# TransistorKeyBoard.net
KiCad netlist of a schematic drawn in Altium Designer
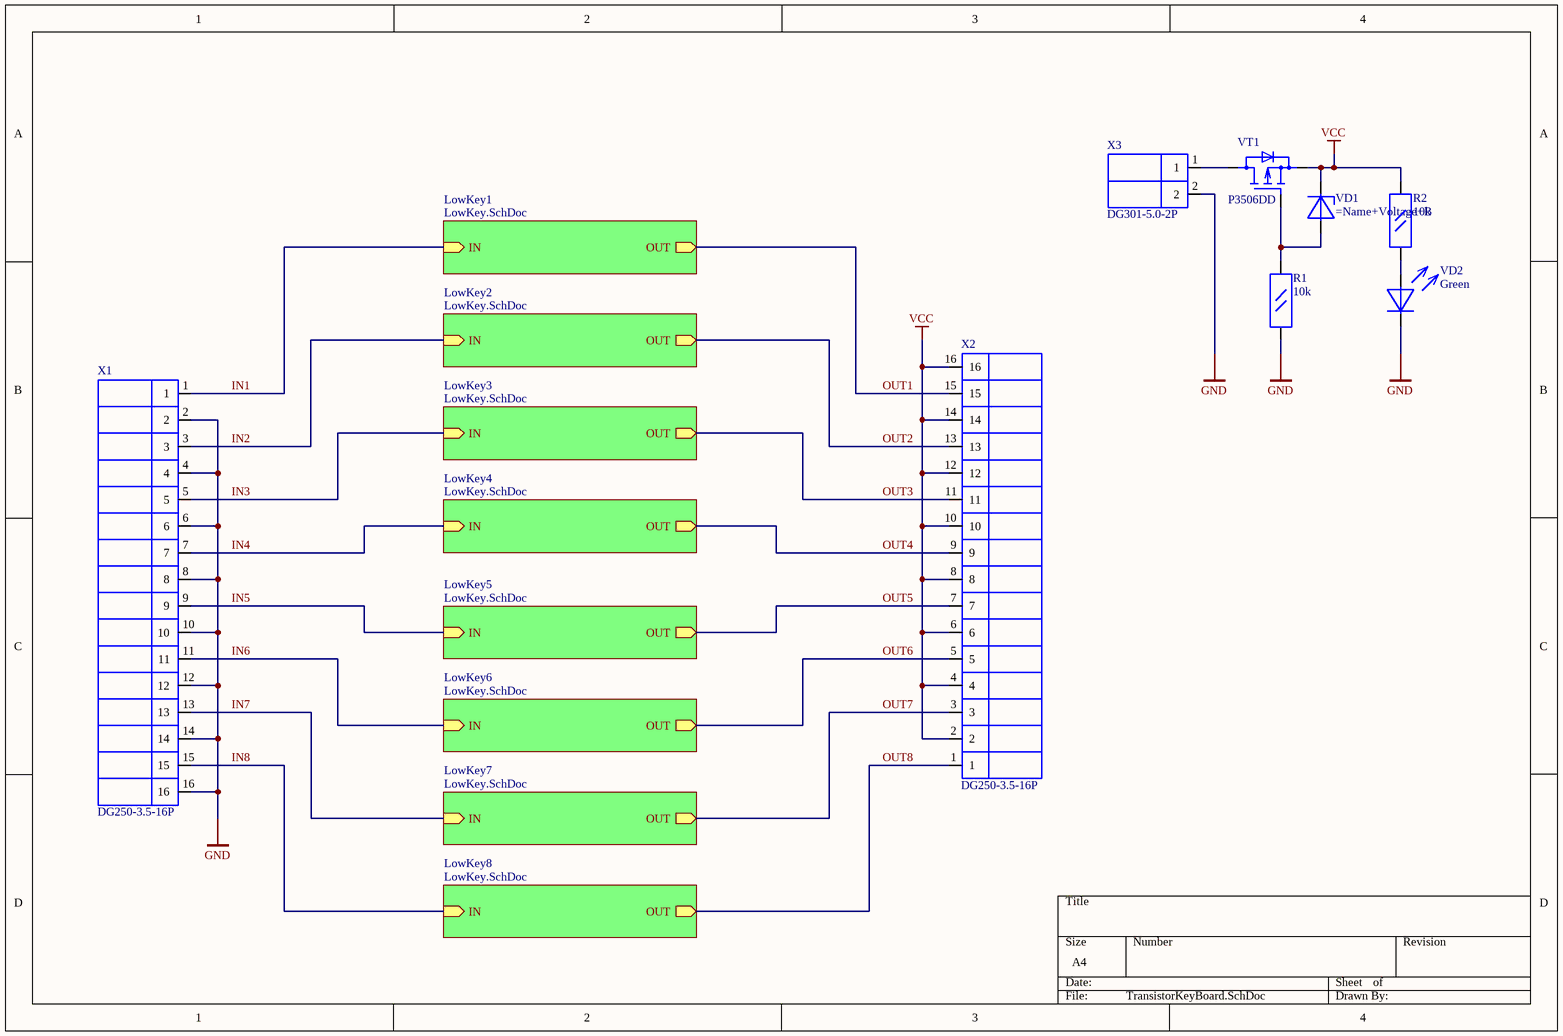
[diagram p0: TransistorKeyBoard.SchDoc]

(export (version "E")
  (design (tool "Eeschema 10.0.6"))
  (components
    (comp (ref "R1")
      (value "R0805")
      (footprint "RES0805")
      (description "Resistor")
      (fields (field (name "RESISTANCE (OHMS)") "10k"))
      (libsource (lib "zvemake_int_lib") (part "R0805"))
    )
    (comp (ref "R2")
      (value "R0805")
      (footprint "RES0805")
      (description "Resistor")
      (fields (field (name "RESISTANCE (OHMS)") "10k"))
      (libsource (lib "zvemake_int_lib") (part "R0805"))
    )
    (comp (ref "VD1")
      (value "PDZ12")
      (footprint "SOD323")
      (description "Diode")
      (fields (field (name "VOLTAGE") "12"))
      (libsource (lib "zvemake_int_lib") (part "PDZ-B"))
    )
    (comp (ref "VD2")
      (value "Led Green 3mm")
      (footprint "3mm led green")
      (description "3mm Green Led 2.54pitch")
      (fields (field (name "COLOR") "Green"))
      (libsource (lib "zvemake_int_lib") (part "Led Green 3mm"))
    )
    (comp (ref "VT1")
      (value "P3506DD")
      (footprint "DPAK")
      (description "P-channel MOSFET transistor")
      (fields (field (name "MANUFACTURER") "NIKO SEMICONDUCTOR CO"))
      (libsource (lib "zvemake_int_lib") (part "P3506DD"))
    )
    (comp (ref "X1")
      (value "DG250-3.5-16P")
      (footprint "DG250-3.5-16P")
      (description "5mm Pitch PCB Terminal Block Connector")
      (libsource (lib "zvemake_int_lib") (part "DG250-3.5-16P"))
    )
    (comp (ref "X2")
      (value "DG250-3.5-16P")
      (footprint "DG250-3.5-16P")
      (description "5mm Pitch PCB Terminal Block Connector")
      (libsource (lib "zvemake_int_lib") (part "DG250-3.5-16P"))
    )
    (comp (ref "X3")
      (value "DG301-5.0-2P")
      (footprint "DG301-5.0-2P")
      (description "5mm Pitch PCB Terminal Block Connector")
      (libsource (lib "zvemake_int_lib") (part "DG301-5.0-2P"))
    )
  )
  (nets
    (net (code "1") (name "/IN1") (class "Default")
      (node (ref "X1") (pin "1") (pinfunction "1_1") (pintype "passive"))
    )
    (net (code "2") (name "/IN2") (class "Default")
      (node (ref "X1") (pin "3") (pinfunction "3_3") (pintype "passive"))
    )
    (net (code "3") (name "/IN3") (class "Default")
      (node (ref "X1") (pin "5") (pinfunction "5_5") (pintype "passive"))
    )
    (net (code "4") (name "/IN4") (class "Default")
      (node (ref "X1") (pin "7") (pinfunction "7_7") (pintype "passive"))
    )
    (net (code "5") (name "/IN5") (class "Default")
      (node (ref "X1") (pin "9") (pinfunction "9_9") (pintype "passive"))
    )
    (net (code "6") (name "/IN6") (class "Default")
      (node (ref "X1") (pin "11") (pinfunction "11_11") (pintype "passive"))
    )
    (net (code "7") (name "/IN7") (class "Default")
      (node (ref "X1") (pin "13") (pinfunction "13_13") (pintype "passive"))
    )
    (net (code "8") (name "/IN8") (class "Default")
      (node (ref "X1") (pin "15") (pinfunction "15_15") (pintype "passive"))
    )
    (net (code "9") (name "/OUT1") (class "Default")
      (node (ref "X2") (pin "15") (pinfunction "15_15") (pintype "passive"))
    )
    (net (code "10") (name "/OUT2") (class "Default")
      (node (ref "X2") (pin "13") (pinfunction "13_13") (pintype "passive"))
    )
    (net (code "11") (name "/OUT3") (class "Default")
      (node (ref "X2") (pin "11") (pinfunction "11_11") (pintype "passive"))
    )
    (net (code "12") (name "/OUT4") (class "Default")
      (node (ref "X2") (pin "9") (pinfunction "9_9") (pintype "passive"))
    )
    (net (code "13") (name "/OUT5") (class "Default")
      (node (ref "X2") (pin "7") (pinfunction "7_7") (pintype "passive"))
    )
    (net (code "14") (name "/OUT6") (class "Default")
      (node (ref "X2") (pin "5") (pinfunction "5_5") (pintype "passive"))
    )
    (net (code "15") (name "/OUT7") (class "Default")
      (node (ref "X2") (pin "3") (pinfunction "3_3") (pintype "passive"))
    )
    (net (code "16") (name "/OUT8") (class "Default")
      (node (ref "X2") (pin "1") (pinfunction "1_1") (pintype "passive"))
    )
    (net (code "17") (name "GND") (class "Default")
      (node (ref "R1") (pin "1") (pinfunction "1_1") (pintype "passive"))
      (node (ref "VD2") (pin "1") (pinfunction "C_1") (pintype "passive"))
      (node (ref "X1") (pin "10") (pinfunction "10_10") (pintype "passive"))
      (node (ref "X1") (pin "12") (pinfunction "12_12") (pintype "passive"))
      (node (ref "X1") (pin "14") (pinfunction "14_14") (pintype "passive"))
      (node (ref "X1") (pin "16") (pinfunction "16_16") (pintype "passive"))
      (node (ref "X1") (pin "2") (pinfunction "2_2") (pintype "passive"))
      (node (ref "X1") (pin "4") (pinfunction "4_4") (pintype "passive"))
      (node (ref "X1") (pin "6") (pinfunction "6_6") (pintype "passive"))
      (node (ref "X1") (pin "8") (pinfunction "8_8") (pintype "passive"))
      (node (ref "X3") (pin "2") (pinfunction "2_2") (pintype "passive"))
    )
    (net (code "18") (name "Net-(VD1-A)") (class "Default")
      (node (ref "R1") (pin "2") (pinfunction "2_2") (pintype "passive"))
      (node (ref "VD1") (pin "2") (pinfunction "A_2") (pintype "passive"))
      (node (ref "VT1") (pin "1") (pinfunction "G_1") (pintype "passive"))
    )
    (net (code "19") (name "Net-(VD2-A)") (class "Default")
      (node (ref "R2") (pin "1") (pinfunction "1_1") (pintype "passive"))
      (node (ref "VD2") (pin "2") (pinfunction "A_2") (pintype "passive"))
    )
    (net (code "20") (name "Net-(VT1-D)") (class "Default")
      (node (ref "VT1") (pin "2") (pinfunction "D_2") (pintype "passive"))
      (node (ref "X3") (pin "1") (pinfunction "1_1") (pintype "passive"))
    )
    (net (code "21") (name "VCC") (class "Default")
      (node (ref "R2") (pin "2") (pinfunction "2_2") (pintype "passive"))
      (node (ref "VD1") (pin "1") (pinfunction "C_1") (pintype "passive"))
      (node (ref "VT1") (pin "3") (pinfunction "S_3") (pintype "passive"))
      (node (ref "X2") (pin "10") (pinfunction "10_10") (pintype "passive"))
      (node (ref "X2") (pin "12") (pinfunction "12_12") (pintype "passive"))
      (node (ref "X2") (pin "14") (pinfunction "14_14") (pintype "passive"))
      (node (ref "X2") (pin "16") (pinfunction "16_16") (pintype "passive"))
      (node (ref "X2") (pin "2") (pinfunction "2_2") (pintype "passive"))
      (node (ref "X2") (pin "4") (pinfunction "4_4") (pintype "passive"))
      (node (ref "X2") (pin "6") (pinfunction "6_6") (pintype "passive"))
      (node (ref "X2") (pin "8") (pinfunction "8_8") (pintype "passive"))
    )
  )
)
